# extruder_breakout.net
KiCad netlist of a schematic drawn in EAGLE
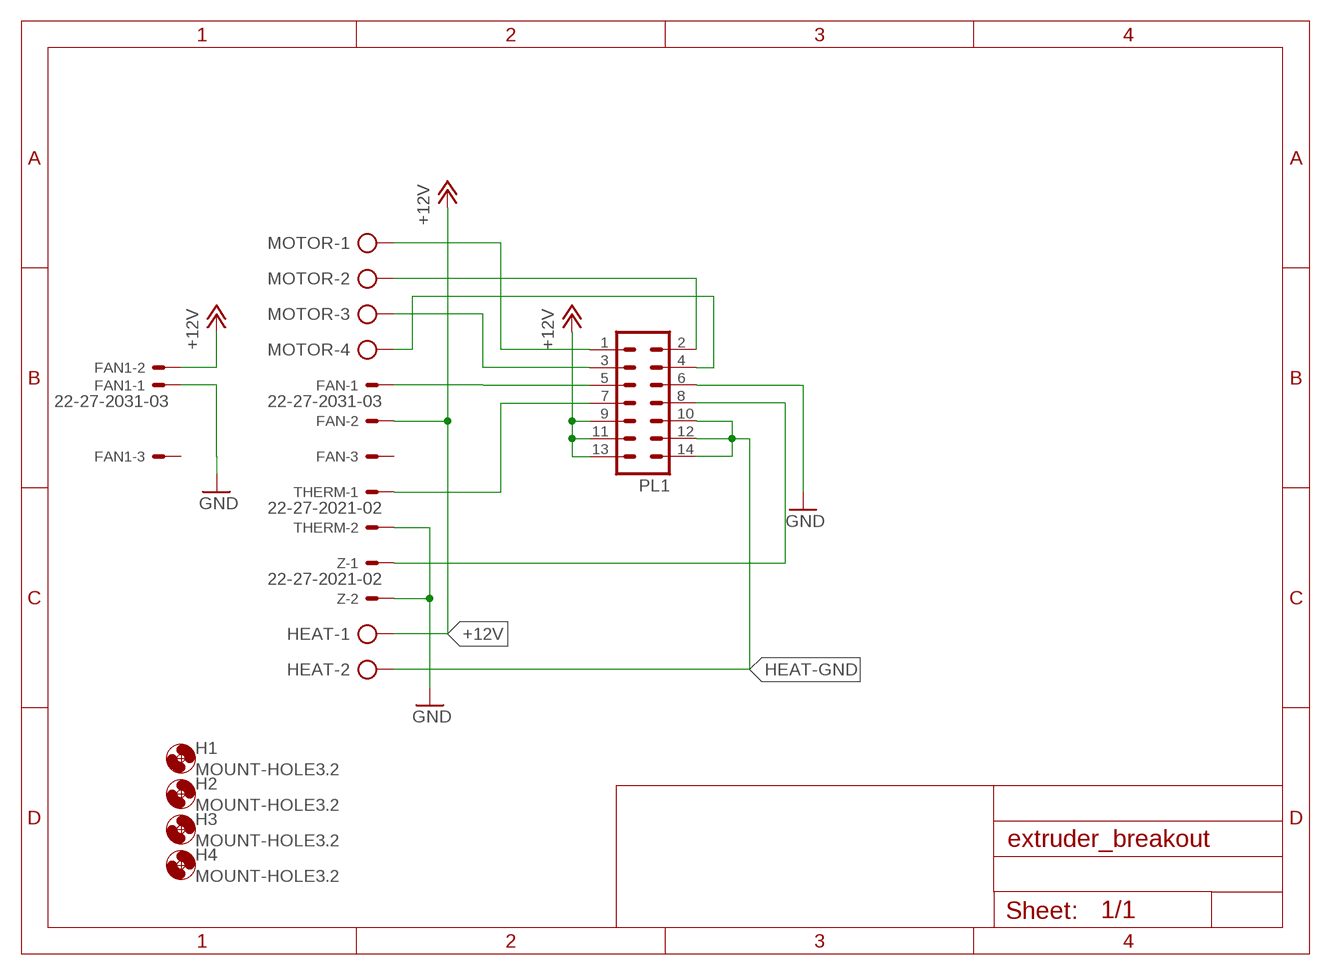
[diagram p0: schematic, sheet 1]

(export (version "E")
  (design (tool "Eeschema 10.0.6"))
  (components
    (comp (ref "FAN")
      (value "22-27-2031-03")
      (footprint "eagle-import:6410-03")
      (libsource (lib "eagle-import") (part "22-?-0327-2031"))
    )
    (comp (ref "FAN1")
      (value "22-27-2031-03")
      (footprint "eagle-import:6410-03")
      (libsource (lib "eagle-import") (part "22-?-0327-2031"))
    )
    (comp (ref "H1")
      (value "MOUNT-HOLE3.2")
      (footprint "eagle-import:3,2")
      (libsource (lib "eagle-import") (part "MOUNT-HOLE3.2"))
    )
    (comp (ref "H2")
      (value "MOUNT-HOLE3.2")
      (footprint "eagle-import:3,2")
      (libsource (lib "eagle-import") (part "MOUNT-HOLE3.2"))
    )
    (comp (ref "H3")
      (value "MOUNT-HOLE3.2")
      (footprint "eagle-import:3,2")
      (libsource (lib "eagle-import") (part "MOUNT-HOLE3.2"))
    )
    (comp (ref "H4")
      (value "MOUNT-HOLE3.2")
      (footprint "eagle-import:3,2")
      (libsource (lib "eagle-import") (part "MOUNT-HOLE3.2"))
    )
    (comp (ref "HEAT")
      (value "AK500/2")
      (footprint "eagle-import:AK500_2")
      (libsource (lib "eagle-import") (part "AK500/2"))
    )
    (comp (ref "MOTOR")
      (value "AK500/4")
      (footprint "eagle-import:AK500_4")
      (libsource (lib "eagle-import") (part "AK500/4"))
    )
    (comp (ref "PL1")
      (value "14V")
      (footprint "eagle-import:14V")
      (libsource (lib "eagle-import") (part "14V"))
    )
    (comp (ref "THERM")
      (value "22-27-2021-02")
      (footprint "eagle-import:6410-02")
      (libsource (lib "eagle-import") (part "22-?-0227-2021"))
    )
    (comp (ref "Z")
      (value "22-27-2021-02")
      (footprint "eagle-import:6410-02")
      (libsource (lib "eagle-import") (part "22-?-0227-2021"))
    )
  )
  (nets
    (net (code "1") (name "+12V") (class "Default")
      (node (ref "FAN") (pin "2") (pinfunction "S_2") (pintype "passive"))
      (node (ref "FAN1") (pin "2") (pinfunction "S_2") (pintype "passive"))
      (node (ref "HEAT") (pin "1") (pinfunction "KL_1") (pintype "passive"))
      (node (ref "PL1") (pin "11") (pinfunction "11_11") (pintype "passive"))
      (node (ref "PL1") (pin "13") (pinfunction "13_13") (pintype "passive"))
      (node (ref "PL1") (pin "9") (pinfunction "9_9") (pintype "passive"))
    )
    (net (code "2") (name "GND") (class "Default")
      (node (ref "FAN1") (pin "1") (pinfunction "S_1") (pintype "passive"))
      (node (ref "PL1") (pin "6") (pinfunction "6_6") (pintype "passive"))
      (node (ref "THERM") (pin "2") (pinfunction "S_2") (pintype "passive"))
      (node (ref "Z") (pin "2") (pinfunction "S_2") (pintype "passive"))
    )
    (net (code "3") (name "HEAT-GND") (class "Default")
      (node (ref "HEAT") (pin "2") (pinfunction "KL_2") (pintype "passive"))
      (node (ref "PL1") (pin "10") (pinfunction "10_10") (pintype "passive"))
      (node (ref "PL1") (pin "12") (pinfunction "12_12") (pintype "passive"))
      (node (ref "PL1") (pin "14") (pinfunction "14_14") (pintype "passive"))
    )
    (net (code "4") (name "Net-(FANA-S)") (class "Default")
      (node (ref "FAN") (pin "1") (pinfunction "S_1") (pintype "passive"))
      (node (ref "PL1") (pin "5") (pinfunction "5_5") (pintype "passive"))
    )
    (net (code "5") (name "Net-(MOTORA-KL)") (class "Default")
      (node (ref "MOTOR") (pin "1") (pinfunction "KL_1") (pintype "passive"))
      (node (ref "PL1") (pin "1") (pinfunction "1_1") (pintype "passive"))
    )
    (net (code "6") (name "Net-(MOTORB-KL)") (class "Default")
      (node (ref "MOTOR") (pin "2") (pinfunction "KL_2") (pintype "passive"))
      (node (ref "PL1") (pin "2") (pinfunction "2_2") (pintype "passive"))
    )
    (net (code "7") (name "Net-(MOTORC-KL)") (class "Default")
      (node (ref "MOTOR") (pin "3") (pinfunction "KL_3") (pintype "passive"))
      (node (ref "PL1") (pin "3") (pinfunction "3_3") (pintype "passive"))
    )
    (net (code "8") (name "Net-(MOTORD-KL)") (class "Default")
      (node (ref "MOTOR") (pin "4") (pinfunction "KL_4") (pintype "passive"))
      (node (ref "PL1") (pin "4") (pinfunction "4_4") (pintype "passive"))
    )
    (net (code "9") (name "Net-(THERMA-S)") (class "Default")
      (node (ref "PL1") (pin "7") (pinfunction "7_7") (pintype "passive"))
      (node (ref "THERM") (pin "1") (pinfunction "S_1") (pintype "passive"))
    )
    (net (code "10") (name "Net-(ZA-S)") (class "Default")
      (node (ref "PL1") (pin "8") (pinfunction "8_8") (pintype "passive"))
      (node (ref "Z") (pin "1") (pinfunction "S_1") (pintype "passive"))
    )
    (net (code "11") (name "unconnected-(FAN1C-S-Pad3)") (class "Default")
      (node (ref "FAN1") (pin "3") (pinfunction "S_3") (pintype "passive"))
    )
    (net (code "12") (name "unconnected-(FANC-S-Pad3)") (class "Default")
      (node (ref "FAN") (pin "3") (pinfunction "S_3") (pintype "passive"))
    )
  )
)
